# PGA.net
KiCad netlist of a schematic drawn in Altium Designer
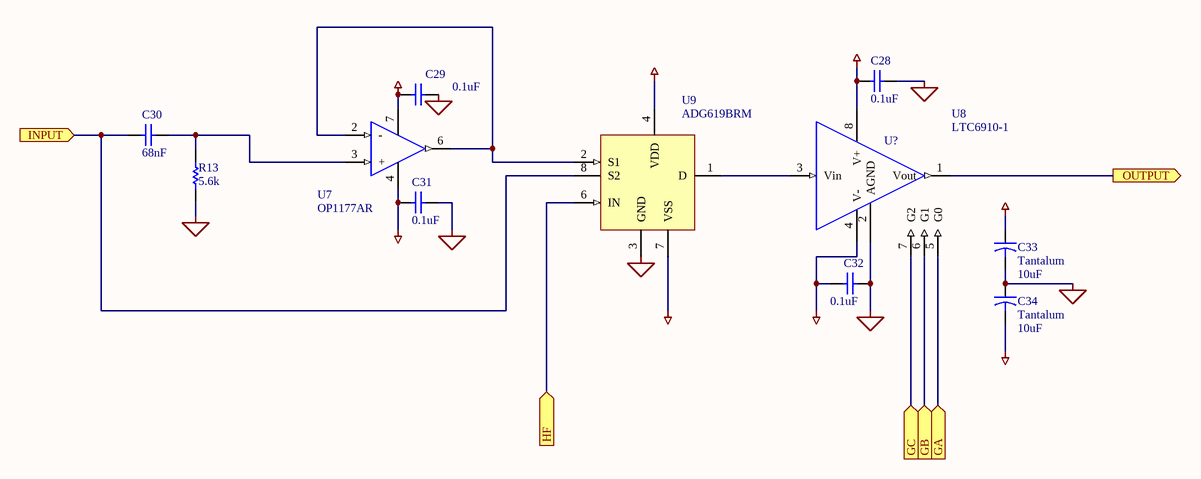
[diagram p0: PGA.SCHDOC]

(export (version "E")
  (design (tool "Eeschema 10.0.6"))
  (components
    (comp (ref "C28")
      (value "0.1uF")
      (footprint "CC1608-0603")
      (description "Capacitor")
      (fields
        (field (name "MANUFACTURER") "Generic Components")
        (field (name "Comment") "Cap")
        (field (name "PUBLISHER") "Altium Limited")
      )
      (libsource (lib "Miscellaneous Devices") (part "Cap"))
    )
    (comp (ref "C29")
      (value "0.1uF")
      (footprint "CC1608-0603")
      (description "Capacitor")
      (fields
        (field (name "MANUFACTURER") "Generic Components")
        (field (name "Comment") "Cap")
        (field (name "PUBLISHER") "Altium Limited")
      )
      (libsource (lib "Miscellaneous Devices") (part "Cap"))
    )
    (comp (ref "C30")
      (value "68nF")
      (footprint "CC1608-0603")
      (description "Capacitor")
      (fields
        (field (name "MANUFACTURER") "Generic Components")
        (field (name "Comment") "Cap")
        (field (name "PUBLISHER") "Altium Limited")
      )
      (libsource (lib "Miscellaneous Devices") (part "Cap"))
    )
    (comp (ref "C31")
      (value "0.1uF")
      (footprint "CC1608-0603")
      (description "Capacitor")
      (fields
        (field (name "MANUFACTURER") "Generic Components")
        (field (name "Comment") "Cap")
        (field (name "PUBLISHER") "Altium Limited")
      )
      (libsource (lib "Miscellaneous Devices") (part "Cap"))
    )
    (comp (ref "C32")
      (value "0.1uF")
      (footprint "CC1608-0603")
      (description "Capacitor")
      (fields
        (field (name "MANUFACTURER") "Generic Components")
        (field (name "Comment") "Cap")
        (field (name "PUBLISHER") "Altium Limited")
      )
      (libsource (lib "Miscellaneous Devices") (part "Cap"))
    )
    (comp (ref "C33")
      (value "Tantalum")
      (footprint "TC3216-1206")
      (description "Capacitor")
      (fields
        (field (name "MANUFACTURER") "Generic Components")
        (field (name "ALTIUM_VALUE") "10uF")
        (field (name "PUBLISHER") "Altium Limited")
      )
      (libsource (lib "Miscellaneous Devices") (part "Cap2"))
    )
    (comp (ref "C34")
      (value "Tantalum")
      (footprint "TC3216-1206")
      (description "Capacitor")
      (fields
        (field (name "MANUFACTURER") "Generic Components")
        (field (name "ALTIUM_VALUE") "10uF")
        (field (name "PUBLISHER") "Altium Limited")
      )
      (libsource (lib "Miscellaneous Devices") (part "Cap2"))
    )
    (comp (ref "R13")
      (value "5.6k")
      (footprint "CC1608-0603")
      (description "Resistor")
      (fields
        (field (name "MANUFACTURER") "Generic Components")
        (field (name "Comment") "Res1")
        (field (name "PUBLISHER") "Altium Limited")
      )
      (libsource (lib "Miscellaneous Devices") (part "Res1"))
    )
    (comp (ref "U7")
      (value "OP1177AR")
      (footprint "TSSO3X5-G8/X.4")
      (description "Precision Low Noise, Low Input Bias Current Operational Amplifier")
      (libsource (lib "parts") (part "OP1177"))
    )
    (comp (ref "U8")
      (value "LTC6910-1")
      (footprint "TSOT-23-8")
      (description "LTI Digitally Controlled Programmabe Gain Amp")
      (libsource (lib "parts") (part "LTC6910-1"))
    )
    (comp (ref "U9")
      (value "ADG619BRM")
      (footprint "MSOP8")
      (description "Low RON SPDT Switch (s2 normally on)")
      (libsource (lib "parts") (part "ADG619"))
    )
  )
  (nets
    (net (code "1") (name "/GA") (class "Default")
      (node (ref "U8") (pin "5") (pinfunction "G0_5") (pintype "input"))
    )
    (net (code "2") (name "/GB") (class "Default")
      (node (ref "U8") (pin "6") (pinfunction "G1_6") (pintype "input"))
    )
    (net (code "3") (name "/GC") (class "Default")
      (node (ref "U8") (pin "7") (pinfunction "G2_7") (pintype "input"))
    )
    (net (code "4") (name "/HF") (class "Default")
      (node (ref "U9") (pin "6") (pinfunction "IN_6") (pintype "input"))
    )
    (net (code "5") (name "/INPUT") (class "Default")
      (node (ref "C30") (pin "2") (pinfunction "2_2") (pintype "passive"))
      (node (ref "U9") (pin "8") (pinfunction "S2_8") (pintype "passive"))
    )
    (net (code "6") (name "/OUTPUT") (class "Default")
      (node (ref "U8") (pin "1") (pinfunction "Vout_1") (pintype "output"))
    )
    (net (code "7") (name "AGND") (class "Default")
      (node (ref "C28") (pin "2") (pinfunction "2_2") (pintype "passive"))
      (node (ref "C29") (pin "2") (pinfunction "2_2") (pintype "passive"))
      (node (ref "C31") (pin "2") (pinfunction "2_2") (pintype "passive"))
      (node (ref "C32") (pin "1") (pinfunction "1_1") (pintype "passive"))
      (node (ref "C33") (pin "2") (pinfunction "2_2") (pintype "passive"))
      (node (ref "C34") (pin "1") (pinfunction "1_1") (pintype "passive"))
      (node (ref "R13") (pin "1") (pinfunction "1_1") (pintype "passive"))
      (node (ref "U8") (pin "2") (pinfunction "AGND_2") (pintype "power_in"))
      (node (ref "U9") (pin "3") (pinfunction "GND_3") (pintype "power_in"))
    )
    (net (code "8") (name "AVDD") (class "Default")
      (node (ref "C28") (pin "1") (pinfunction "1_1") (pintype "passive"))
      (node (ref "C29") (pin "1") (pinfunction "1_1") (pintype "passive"))
      (node (ref "C33") (pin "1") (pinfunction "1_1") (pintype "passive"))
      (node (ref "U7") (pin "7") (pinfunction "+Vs_7") (pintype "power_in"))
      (node (ref "U8") (pin "8") (pinfunction "V+_8") (pintype "power_in"))
      (node (ref "U9") (pin "4") (pinfunction "VDD_4") (pintype "power_in"))
    )
    (net (code "9") (name "AVSS") (class "Default")
      (node (ref "C31") (pin "1") (pinfunction "1_1") (pintype "passive"))
      (node (ref "C32") (pin "2") (pinfunction "2_2") (pintype "passive"))
      (node (ref "C34") (pin "2") (pinfunction "2_2") (pintype "passive"))
      (node (ref "U7") (pin "4") (pinfunction "-Vs_4") (pintype "power_in"))
      (node (ref "U8") (pin "4") (pinfunction "V-_4") (pintype "power_in"))
      (node (ref "U9") (pin "7") (pinfunction "VSS_7") (pintype "power_in"))
    )
    (net (code "10") (name "Net-(U7-+)") (class "Default")
      (node (ref "C30") (pin "1") (pinfunction "1_1") (pintype "passive"))
      (node (ref "R13") (pin "2") (pinfunction "2_2") (pintype "passive"))
      (node (ref "U7") (pin "3") (pinfunction "+_3") (pintype "input"))
    )
    (net (code "11") (name "Net-(U7--)") (class "Default")
      (node (ref "U7") (pin "2") (pinfunction "-_2") (pintype "input"))
      (node (ref "U7") (pin "6") (pinfunction "Out_6") (pintype "output"))
      (node (ref "U9") (pin "2") (pinfunction "S1_2") (pintype "input"))
    )
    (net (code "12") (name "Net-(U8-Vin)") (class "Default")
      (node (ref "U8") (pin "3") (pinfunction "Vin_3") (pintype "input"))
      (node (ref "U9") (pin "1") (pinfunction "D_1") (pintype "passive"))
    )
  )
)
